# SuperCapacitor_Schmatic.net
KiCad netlist of a schematic drawn in EAGLE
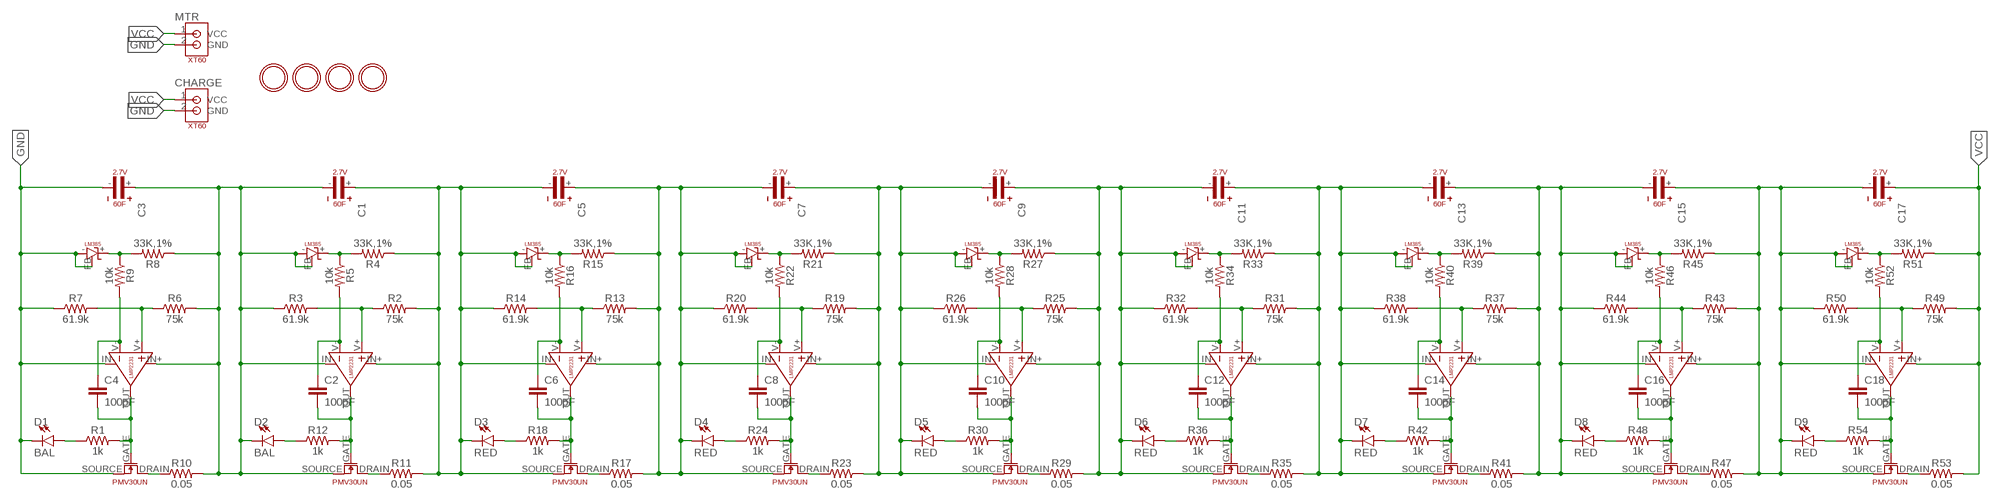
[diagram p0: schematic, sheet 1]

(export (version "E")
  (design (tool "Eeschema 10.0.6"))
  (components
    (comp (ref "C1")
      (value "2.7V 60F")
      (footprint "eagle-import:2.7V_60F")
      (libsource (lib "eagle-import") (part "2.7V_60F"))
    )
    (comp (ref "C2")
      (value "100pF")
      (footprint "eagle-import:0603")
      (libsource (lib "eagle-import") (part "100PF-0603-50V-5%"))
    )
    (comp (ref "C3")
      (value "2.7V 60F")
      (footprint "eagle-import:2.7V_60F")
      (libsource (lib "eagle-import") (part "2.7V_60F"))
    )
    (comp (ref "C4")
      (value "100pF")
      (footprint "eagle-import:0603")
      (libsource (lib "eagle-import") (part "100PF-0603-50V-5%"))
    )
    (comp (ref "C5")
      (value "2.7V 60F")
      (footprint "eagle-import:2.7V_60F")
      (libsource (lib "eagle-import") (part "2.7V_60F"))
    )
    (comp (ref "C6")
      (value "100pF")
      (footprint "eagle-import:0603")
      (libsource (lib "eagle-import") (part "100PF-0603-50V-5%"))
    )
    (comp (ref "C7")
      (value "2.7V 60F")
      (footprint "eagle-import:2.7V_60F")
      (libsource (lib "eagle-import") (part "2.7V_60F"))
    )
    (comp (ref "C8")
      (value "100pF")
      (footprint "eagle-import:0603")
      (libsource (lib "eagle-import") (part "100PF-0603-50V-5%"))
    )
    (comp (ref "C9")
      (value "2.7V 60F")
      (footprint "eagle-import:2.7V_60F")
      (libsource (lib "eagle-import") (part "2.7V_60F"))
    )
    (comp (ref "C10")
      (value "100pF")
      (footprint "eagle-import:0603")
      (libsource (lib "eagle-import") (part "100PF-0603-50V-5%"))
    )
    (comp (ref "C11")
      (value "2.7V 60F")
      (footprint "eagle-import:2.7V_60F")
      (libsource (lib "eagle-import") (part "2.7V_60F"))
    )
    (comp (ref "C12")
      (value "100pF")
      (footprint "eagle-import:0603")
      (libsource (lib "eagle-import") (part "100PF-0603-50V-5%"))
    )
    (comp (ref "C13")
      (value "2.7V 60F")
      (footprint "eagle-import:2.7V_60F")
      (libsource (lib "eagle-import") (part "2.7V_60F"))
    )
    (comp (ref "C14")
      (value "100pF")
      (footprint "eagle-import:0603")
      (libsource (lib "eagle-import") (part "100PF-0603-50V-5%"))
    )
    (comp (ref "C15")
      (value "2.7V 60F")
      (footprint "eagle-import:2.7V_60F")
      (libsource (lib "eagle-import") (part "2.7V_60F"))
    )
    (comp (ref "C16")
      (value "100pF")
      (footprint "eagle-import:0603")
      (libsource (lib "eagle-import") (part "100PF-0603-50V-5%"))
    )
    (comp (ref "C17")
      (value "2.7V 60F")
      (footprint "eagle-import:2.7V_60F")
      (libsource (lib "eagle-import") (part "2.7V_60F"))
    )
    (comp (ref "C18")
      (value "100pF")
      (footprint "eagle-import:0603")
      (libsource (lib "eagle-import") (part "100PF-0603-50V-5%"))
    )
    (comp (ref "CHARGE")
      (value "XT60")
      (footprint "eagle-import:XT60")
      (libsource (lib "eagle-import") (part "XT60"))
    )
    (comp (ref "D1")
      (value "BAL")
      (footprint "eagle-import:LED-0603")
      (libsource (lib "eagle-import") (part "LED-RED0603"))
    )
    (comp (ref "D2")
      (value "BAL")
      (footprint "eagle-import:LED-0603")
      (libsource (lib "eagle-import") (part "LED-RED0603"))
    )
    (comp (ref "D3")
      (value "RED")
      (footprint "eagle-import:LED-0603")
      (libsource (lib "eagle-import") (part "LED-RED0603"))
    )
    (comp (ref "D4")
      (value "RED")
      (footprint "eagle-import:LED-0603")
      (libsource (lib "eagle-import") (part "LED-RED0603"))
    )
    (comp (ref "D5")
      (value "RED")
      (footprint "eagle-import:LED-0603")
      (libsource (lib "eagle-import") (part "LED-RED0603"))
    )
    (comp (ref "D6")
      (value "RED")
      (footprint "eagle-import:LED-0603")
      (libsource (lib "eagle-import") (part "LED-RED0603"))
    )
    (comp (ref "D7")
      (value "RED")
      (footprint "eagle-import:LED-0603")
      (libsource (lib "eagle-import") (part "LED-RED0603"))
    )
    (comp (ref "D8")
      (value "RED")
      (footprint "eagle-import:LED-0603")
      (libsource (lib "eagle-import") (part "LED-RED0603"))
    )
    (comp (ref "D9")
      (value "RED")
      (footprint "eagle-import:LED-0603")
      (libsource (lib "eagle-import") (part "LED-RED0603"))
    )
    (comp (ref "MTR")
      (value "XT60")
      (footprint "eagle-import:XT60")
      (libsource (lib "eagle-import") (part "XT60"))
    )
    (comp (ref "R1")
      (value "1k")
      (footprint "eagle-import:0603")
      (libsource (lib "eagle-import") (part "1KOHM-0603-1/10W-1%"))
    )
    (comp (ref "R2")
      (value "75k")
      (footprint "eagle-import:0603")
      (libsource (lib "eagle-import") (part "75KOHM-0603-1/10W-1%"))
    )
    (comp (ref "R3")
      (value "61.9k")
      (footprint "eagle-import:0603")
      (libsource (lib "eagle-import") (part "75KOHM-0603-1/10W-1%"))
    )
    (comp (ref "R4")
      (value "33K,1%")
      (footprint "eagle-import:0603")
      (libsource (lib "eagle-import") (part "1MOHM-0603-1/4W-5%"))
    )
    (comp (ref "R5")
      (value "10k")
      (footprint "eagle-import:0603")
      (libsource (lib "eagle-import") (part "10KOHM-0603-1/10W-1%"))
    )
    (comp (ref "R6")
      (value "75k")
      (footprint "eagle-import:0603")
      (libsource (lib "eagle-import") (part "75KOHM-0603-1/10W-1%"))
    )
    (comp (ref "R7")
      (value "61.9k")
      (footprint "eagle-import:0603")
      (libsource (lib "eagle-import") (part "75KOHM-0603-1/10W-1%"))
    )
    (comp (ref "R8")
      (value "33K,1%")
      (footprint "eagle-import:0603")
      (libsource (lib "eagle-import") (part "1MOHM-0603-1/4W-5%"))
    )
    (comp (ref "R9")
      (value "10k")
      (footprint "eagle-import:0603")
      (libsource (lib "eagle-import") (part "10KOHM-0603-1/10W-1%"))
    )
    (comp (ref "R10")
      (value "0.05")
      (footprint "eagle-import:2512")
      (libsource (lib "eagle-import") (part "0.05OHM-2512-3W-1%"))
    )
    (comp (ref "R11")
      (value "0.05")
      (footprint "eagle-import:2512")
      (libsource (lib "eagle-import") (part "0.05OHM-2512-3W-1%"))
    )
    (comp (ref "R12")
      (value "1k")
      (footprint "eagle-import:0603")
      (libsource (lib "eagle-import") (part "1KOHM-0603-1/10W-1%"))
    )
    (comp (ref "R13")
      (value "75k")
      (footprint "eagle-import:0603")
      (libsource (lib "eagle-import") (part "75KOHM-0603-1/10W-1%"))
    )
    (comp (ref "R14")
      (value "61.9k")
      (footprint "eagle-import:0603")
      (libsource (lib "eagle-import") (part "75KOHM-0603-1/10W-1%"))
    )
    (comp (ref "R15")
      (value "33K,1%")
      (footprint "eagle-import:0603")
      (libsource (lib "eagle-import") (part "1MOHM-0603-1/4W-5%"))
    )
    (comp (ref "R16")
      (value "10k")
      (footprint "eagle-import:0603")
      (libsource (lib "eagle-import") (part "10KOHM-0603-1/10W-1%"))
    )
    (comp (ref "R17")
      (value "0.05")
      (footprint "eagle-import:2512")
      (libsource (lib "eagle-import") (part "0.05OHM-2512-3W-1%"))
    )
    (comp (ref "R18")
      (value "1k")
      (footprint "eagle-import:0603")
      (libsource (lib "eagle-import") (part "1KOHM-0603-1/10W-1%"))
    )
    (comp (ref "R19")
      (value "75k")
      (footprint "eagle-import:0603")
      (libsource (lib "eagle-import") (part "75KOHM-0603-1/10W-1%"))
    )
    (comp (ref "R20")
      (value "61.9k")
      (footprint "eagle-import:0603")
      (libsource (lib "eagle-import") (part "75KOHM-0603-1/10W-1%"))
    )
    (comp (ref "R21")
      (value "33K,1%")
      (footprint "eagle-import:0603")
      (libsource (lib "eagle-import") (part "1MOHM-0603-1/4W-5%"))
    )
    (comp (ref "R22")
      (value "10k")
      (footprint "eagle-import:0603")
      (libsource (lib "eagle-import") (part "10KOHM-0603-1/10W-1%"))
    )
    (comp (ref "R23")
      (value "0.05")
      (footprint "eagle-import:2512")
      (libsource (lib "eagle-import") (part "0.05OHM-2512-3W-1%"))
    )
    (comp (ref "R24")
      (value "1k")
      (footprint "eagle-import:0603")
      (libsource (lib "eagle-import") (part "1KOHM-0603-1/10W-1%"))
    )
    (comp (ref "R25")
      (value "75k")
      (footprint "eagle-import:0603")
      (libsource (lib "eagle-import") (part "75KOHM-0603-1/10W-1%"))
    )
    (comp (ref "R26")
      (value "61.9k")
      (footprint "eagle-import:0603")
      (libsource (lib "eagle-import") (part "75KOHM-0603-1/10W-1%"))
    )
    (comp (ref "R27")
      (value "33K,1%")
      (footprint "eagle-import:0603")
      (libsource (lib "eagle-import") (part "1MOHM-0603-1/4W-5%"))
    )
    (comp (ref "R28")
      (value "10k")
      (footprint "eagle-import:0603")
      (libsource (lib "eagle-import") (part "10KOHM-0603-1/10W-1%"))
    )
    (comp (ref "R29")
      (value "0.05")
      (footprint "eagle-import:2512")
      (libsource (lib "eagle-import") (part "0.05OHM-2512-3W-1%"))
    )
    (comp (ref "R30")
      (value "1k")
      (footprint "eagle-import:0603")
      (libsource (lib "eagle-import") (part "1KOHM-0603-1/10W-1%"))
    )
    (comp (ref "R31")
      (value "75k")
      (footprint "eagle-import:0603")
      (libsource (lib "eagle-import") (part "75KOHM-0603-1/10W-1%"))
    )
    (comp (ref "R32")
      (value "61.9k")
      (footprint "eagle-import:0603")
      (libsource (lib "eagle-import") (part "75KOHM-0603-1/10W-1%"))
    )
    (comp (ref "R33")
      (value "33K,1%")
      (footprint "eagle-import:0603")
      (libsource (lib "eagle-import") (part "1MOHM-0603-1/4W-5%"))
    )
    (comp (ref "R34")
      (value "10k")
      (footprint "eagle-import:0603")
      (libsource (lib "eagle-import") (part "10KOHM-0603-1/10W-1%"))
    )
    (comp (ref "R35")
      (value "0.05")
      (footprint "eagle-import:2512")
      (libsource (lib "eagle-import") (part "0.05OHM-2512-3W-1%"))
    )
    (comp (ref "R36")
      (value "1k")
      (footprint "eagle-import:0603")
      (libsource (lib "eagle-import") (part "1KOHM-0603-1/10W-1%"))
    )
    (comp (ref "R37")
      (value "75k")
      (footprint "eagle-import:0603")
      (libsource (lib "eagle-import") (part "75KOHM-0603-1/10W-1%"))
    )
    (comp (ref "R38")
      (value "61.9k")
      (footprint "eagle-import:0603")
      (libsource (lib "eagle-import") (part "75KOHM-0603-1/10W-1%"))
    )
    (comp (ref "R39")
      (value "33K,1%")
      (footprint "eagle-import:0603")
      (libsource (lib "eagle-import") (part "1MOHM-0603-1/4W-5%"))
    )
    (comp (ref "R40")
      (value "10k")
      (footprint "eagle-import:0603")
      (libsource (lib "eagle-import") (part "10KOHM-0603-1/10W-1%"))
    )
    (comp (ref "R41")
      (value "0.05")
      (footprint "eagle-import:2512")
      (libsource (lib "eagle-import") (part "0.05OHM-2512-3W-1%"))
    )
    (comp (ref "R42")
      (value "1k")
      (footprint "eagle-import:0603")
      (libsource (lib "eagle-import") (part "1KOHM-0603-1/10W-1%"))
    )
    (comp (ref "R43")
      (value "75k")
      (footprint "eagle-import:0603")
      (libsource (lib "eagle-import") (part "75KOHM-0603-1/10W-1%"))
    )
    (comp (ref "R44")
      (value "61.9k")
      (footprint "eagle-import:0603")
      (libsource (lib "eagle-import") (part "75KOHM-0603-1/10W-1%"))
    )
    (comp (ref "R45")
      (value "33K,1%")
      (footprint "eagle-import:0603")
      (libsource (lib "eagle-import") (part "1MOHM-0603-1/4W-5%"))
    )
    (comp (ref "R46")
      (value "10k")
      (footprint "eagle-import:0603")
      (libsource (lib "eagle-import") (part "10KOHM-0603-1/10W-1%"))
    )
    (comp (ref "R47")
      (value "0.05")
      (footprint "eagle-import:2512")
      (libsource (lib "eagle-import") (part "0.05OHM-2512-3W-1%"))
    )
    (comp (ref "R48")
      (value "1k")
      (footprint "eagle-import:0603")
      (libsource (lib "eagle-import") (part "1KOHM-0603-1/10W-1%"))
    )
    (comp (ref "R49")
      (value "75k")
      (footprint "eagle-import:0603")
      (libsource (lib "eagle-import") (part "75KOHM-0603-1/10W-1%"))
    )
    (comp (ref "R50")
      (value "61.9k")
      (footprint "eagle-import:0603")
      (libsource (lib "eagle-import") (part "75KOHM-0603-1/10W-1%"))
    )
    (comp (ref "R51")
      (value "33K,1%")
      (footprint "eagle-import:0603")
      (libsource (lib "eagle-import") (part "1MOHM-0603-1/4W-5%"))
    )
    (comp (ref "R52")
      (value "10k")
      (footprint "eagle-import:0603")
      (libsource (lib "eagle-import") (part "10KOHM-0603-1/10W-1%"))
    )
    (comp (ref "R53")
      (value "0.05")
      (footprint "eagle-import:2512")
      (libsource (lib "eagle-import") (part "0.05OHM-2512-3W-1%"))
    )
    (comp (ref "R54")
      (value "1k")
      (footprint "eagle-import:0603")
      (libsource (lib "eagle-import") (part "1KOHM-0603-1/10W-1%"))
    )
    (comp (ref "U$1")
      (value "LMP2231")
      (footprint "eagle-import:LMP2231_SOT23_5")
      (libsource (lib "eagle-import") (part "LMP2231"))
    )
    (comp (ref "U$2")
      (value "LM385")
      (footprint "eagle-import:LM385_SOT23")
      (libsource (lib "eagle-import") (part "LM385"))
    )
    (comp (ref "U$3")
      (value "PMV30UN_MOS")
      (footprint "eagle-import:PMV30UN_SOT23")
      (libsource (lib "eagle-import") (part "PMV30UN_MOS"))
    )
    (comp (ref "U$4")
      (value "LMP2231")
      (footprint "eagle-import:LMP2231_SOT23_5")
      (libsource (lib "eagle-import") (part "LMP2231"))
    )
    (comp (ref "U$5")
      (value "LM385")
      (footprint "eagle-import:LM385_SOT23")
      (libsource (lib "eagle-import") (part "LM385"))
    )
    (comp (ref "U$6")
      (value "PMV30UN_MOS")
      (footprint "eagle-import:PMV30UN_SOT23")
      (libsource (lib "eagle-import") (part "PMV30UN_MOS"))
    )
    (comp (ref "U$7")
      (value "LMP2231")
      (footprint "eagle-import:LMP2231_SOT23_5")
      (libsource (lib "eagle-import") (part "LMP2231"))
    )
    (comp (ref "U$8")
      (value "LM385")
      (footprint "eagle-import:LM385_SOT23")
      (libsource (lib "eagle-import") (part "LM385"))
    )
    (comp (ref "U$9")
      (value "PMV30UN_MOS")
      (footprint "eagle-import:PMV30UN_SOT23")
      (libsource (lib "eagle-import") (part "PMV30UN_MOS"))
    )
    (comp (ref "U$10")
      (value "LMP2231")
      (footprint "eagle-import:LMP2231_SOT23_5")
      (libsource (lib "eagle-import") (part "LMP2231"))
    )
    (comp (ref "U$11")
      (value "LM385")
      (footprint "eagle-import:LM385_SOT23")
      (libsource (lib "eagle-import") (part "LM385"))
    )
    (comp (ref "U$12")
      (value "PMV30UN_MOS")
      (footprint "eagle-import:PMV30UN_SOT23")
      (libsource (lib "eagle-import") (part "PMV30UN_MOS"))
    )
    (comp (ref "U$13")
      (value "LMP2231")
      (footprint "eagle-import:LMP2231_SOT23_5")
      (libsource (lib "eagle-import") (part "LMP2231"))
    )
    (comp (ref "U$14")
      (value "LM385")
      (footprint "eagle-import:LM385_SOT23")
      (libsource (lib "eagle-import") (part "LM385"))
    )
    (comp (ref "U$15")
      (value "PMV30UN_MOS")
      (footprint "eagle-import:PMV30UN_SOT23")
      (libsource (lib "eagle-import") (part "PMV30UN_MOS"))
    )
    (comp (ref "U$16")
      (value "LMP2231")
      (footprint "eagle-import:LMP2231_SOT23_5")
      (libsource (lib "eagle-import") (part "LMP2231"))
    )
    (comp (ref "U$17")
      (value "LM385")
      (footprint "eagle-import:LM385_SOT23")
      (libsource (lib "eagle-import") (part "LM385"))
    )
    (comp (ref "U$18")
      (value "PMV30UN_MOS")
      (footprint "eagle-import:PMV30UN_SOT23")
      (libsource (lib "eagle-import") (part "PMV30UN_MOS"))
    )
    (comp (ref "U$19")
      (value "LMP2231")
      (footprint "eagle-import:LMP2231_SOT23_5")
      (libsource (lib "eagle-import") (part "LMP2231"))
    )
    (comp (ref "U$20")
      (value "LM385")
      (footprint "eagle-import:LM385_SOT23")
      (libsource (lib "eagle-import") (part "LM385"))
    )
    (comp (ref "U$21")
      (value "PMV30UN_MOS")
      (footprint "eagle-import:PMV30UN_SOT23")
      (libsource (lib "eagle-import") (part "PMV30UN_MOS"))
    )
    (comp (ref "U$22")
      (value "LMP2231")
      (footprint "eagle-import:LMP2231_SOT23_5")
      (libsource (lib "eagle-import") (part "LMP2231"))
    )
    (comp (ref "U$23")
      (value "LM385")
      (footprint "eagle-import:LM385_SOT23")
      (libsource (lib "eagle-import") (part "LM385"))
    )
    (comp (ref "U$24")
      (value "PMV30UN_MOS")
      (footprint "eagle-import:PMV30UN_SOT23")
      (libsource (lib "eagle-import") (part "PMV30UN_MOS"))
    )
    (comp (ref "U$25")
      (value "LMP2231")
      (footprint "eagle-import:LMP2231_SOT23_5")
      (libsource (lib "eagle-import") (part "LMP2231"))
    )
    (comp (ref "U$26")
      (value "LM385")
      (footprint "eagle-import:LM385_SOT23")
      (libsource (lib "eagle-import") (part "LM385"))
    )
    (comp (ref "U$27")
      (value "PMV30UN_MOS")
      (footprint "eagle-import:PMV30UN_SOT23")
      (libsource (lib "eagle-import") (part "PMV30UN_MOS"))
    )
    (comp (ref "U$30")
      (value "M5")
      (footprint "eagle-import:M5")
      (libsource (lib "eagle-import") (part "M5"))
    )
    (comp (ref "U$31")
      (value "M5")
      (footprint "eagle-import:M5")
      (libsource (lib "eagle-import") (part "M5"))
    )
    (comp (ref "U$32")
      (value "M5")
      (footprint "eagle-import:M5")
      (libsource (lib "eagle-import") (part "M5"))
    )
    (comp (ref "U$33")
      (value "M5")
      (footprint "eagle-import:M5")
      (libsource (lib "eagle-import") (part "M5"))
    )
  )
  (nets
    (net (code "1") (name "GND") (class "Default")
      (node (ref "C3") (pin "-") (pinfunction "-_-") (pintype "bidirectional"))
      (node (ref "CHARGE") (pin "2") (pinfunction "GND_2") (pintype "bidirectional"))
      (node (ref "D1") (pin "C") (pinfunction "C_C") (pintype "passive"))
      (node (ref "MTR") (pin "2") (pinfunction "GND_2") (pintype "bidirectional"))
      (node (ref "R7") (pin "1") (pinfunction "1_1") (pintype "passive"))
      (node (ref "U$4") (pin "IN-") (pinfunction "IN-_IN-") (pintype "bidirectional"))
      (node (ref "U$5") (pin "-") (pinfunction "-_-") (pintype "bidirectional"))
      (node (ref "U$5") (pin "FB") (pinfunction "FB_FB") (pintype "bidirectional"))
      (node (ref "U$6") (pin "SOURCE") (pinfunction "SOURCE_SOURCE") (pintype "bidirectional"))
    )
    (net (code "2") (name "Net-(C2-Pad1)") (class "Default")
      (node (ref "C2") (pin "1") (pinfunction "1_1") (pintype "passive"))
      (node (ref "R5") (pin "2") (pinfunction "2_2") (pintype "passive"))
      (node (ref "U$1") (pin "V-") (pinfunction "V-_V-") (pintype "bidirectional"))
    )
    (net (code "3") (name "Net-(C2-Pad2)") (class "Default")
      (node (ref "C2") (pin "2") (pinfunction "2_2") (pintype "passive"))
      (node (ref "R12") (pin "2") (pinfunction "2_2") (pintype "passive"))
      (node (ref "U$1") (pin "OUT") (pinfunction "OUT_OUT") (pintype "bidirectional"))
      (node (ref "U$3") (pin "GATE") (pinfunction "GATE_GATE") (pintype "bidirectional"))
    )
    (net (code "4") (name "Net-(C4-Pad1)") (class "Default")
      (node (ref "C4") (pin "1") (pinfunction "1_1") (pintype "passive"))
      (node (ref "R9") (pin "2") (pinfunction "2_2") (pintype "passive"))
      (node (ref "U$4") (pin "V-") (pinfunction "V-_V-") (pintype "bidirectional"))
    )
    (net (code "5") (name "Net-(C4-Pad2)") (class "Default")
      (node (ref "C4") (pin "2") (pinfunction "2_2") (pintype "passive"))
      (node (ref "R1") (pin "2") (pinfunction "2_2") (pintype "passive"))
      (node (ref "U$4") (pin "OUT") (pinfunction "OUT_OUT") (pintype "bidirectional"))
      (node (ref "U$6") (pin "GATE") (pinfunction "GATE_GATE") (pintype "bidirectional"))
    )
    (net (code "6") (name "Net-(C6-Pad1)") (class "Default")
      (node (ref "C6") (pin "1") (pinfunction "1_1") (pintype "passive"))
      (node (ref "R16") (pin "2") (pinfunction "2_2") (pintype "passive"))
      (node (ref "U$7") (pin "V-") (pinfunction "V-_V-") (pintype "bidirectional"))
    )
    (net (code "7") (name "Net-(C6-Pad2)") (class "Default")
      (node (ref "C6") (pin "2") (pinfunction "2_2") (pintype "passive"))
      (node (ref "R18") (pin "2") (pinfunction "2_2") (pintype "passive"))
      (node (ref "U$7") (pin "OUT") (pinfunction "OUT_OUT") (pintype "bidirectional"))
      (node (ref "U$9") (pin "GATE") (pinfunction "GATE_GATE") (pintype "bidirectional"))
    )
    (net (code "8") (name "Net-(C8-Pad1)") (class "Default")
      (node (ref "C8") (pin "1") (pinfunction "1_1") (pintype "passive"))
      (node (ref "R22") (pin "2") (pinfunction "2_2") (pintype "passive"))
      (node (ref "U$10") (pin "V-") (pinfunction "V-_V-") (pintype "bidirectional"))
    )
    (net (code "9") (name "Net-(C8-Pad2)") (class "Default")
      (node (ref "C8") (pin "2") (pinfunction "2_2") (pintype "passive"))
      (node (ref "R24") (pin "2") (pinfunction "2_2") (pintype "passive"))
      (node (ref "U$10") (pin "OUT") (pinfunction "OUT_OUT") (pintype "bidirectional"))
      (node (ref "U$12") (pin "GATE") (pinfunction "GATE_GATE") (pintype "bidirectional"))
    )
    (net (code "10") (name "Net-(C10-Pad1)") (class "Default")
      (node (ref "C10") (pin "1") (pinfunction "1_1") (pintype "passive"))
      (node (ref "R28") (pin "2") (pinfunction "2_2") (pintype "passive"))
      (node (ref "U$13") (pin "V-") (pinfunction "V-_V-") (pintype "bidirectional"))
    )
    (net (code "11") (name "Net-(C10-Pad2)") (class "Default")
      (node (ref "C10") (pin "2") (pinfunction "2_2") (pintype "passive"))
      (node (ref "R30") (pin "2") (pinfunction "2_2") (pintype "passive"))
      (node (ref "U$13") (pin "OUT") (pinfunction "OUT_OUT") (pintype "bidirectional"))
      (node (ref "U$15") (pin "GATE") (pinfunction "GATE_GATE") (pintype "bidirectional"))
    )
    (net (code "12") (name "Net-(C12-Pad1)") (class "Default")
      (node (ref "C12") (pin "1") (pinfunction "1_1") (pintype "passive"))
      (node (ref "R34") (pin "2") (pinfunction "2_2") (pintype "passive"))
      (node (ref "U$16") (pin "V-") (pinfunction "V-_V-") (pintype "bidirectional"))
    )
    (net (code "13") (name "Net-(C12-Pad2)") (class "Default")
      (node (ref "C12") (pin "2") (pinfunction "2_2") (pintype "passive"))
      (node (ref "R36") (pin "2") (pinfunction "2_2") (pintype "passive"))
      (node (ref "U$16") (pin "OUT") (pinfunction "OUT_OUT") (pintype "bidirectional"))
      (node (ref "U$18") (pin "GATE") (pinfunction "GATE_GATE") (pintype "bidirectional"))
    )
    (net (code "14") (name "Net-(C14-Pad1)") (class "Default")
      (node (ref "C14") (pin "1") (pinfunction "1_1") (pintype "passive"))
      (node (ref "R40") (pin "2") (pinfunction "2_2") (pintype "passive"))
      (node (ref "U$19") (pin "V-") (pinfunction "V-_V-") (pintype "bidirectional"))
    )
    (net (code "15") (name "Net-(C14-Pad2)") (class "Default")
      (node (ref "C14") (pin "2") (pinfunction "2_2") (pintype "passive"))
      (node (ref "R42") (pin "2") (pinfunction "2_2") (pintype "passive"))
      (node (ref "U$19") (pin "OUT") (pinfunction "OUT_OUT") (pintype "bidirectional"))
      (node (ref "U$21") (pin "GATE") (pinfunction "GATE_GATE") (pintype "bidirectional"))
    )
    (net (code "16") (name "Net-(C16-Pad1)") (class "Default")
      (node (ref "C16") (pin "1") (pinfunction "1_1") (pintype "passive"))
      (node (ref "R46") (pin "2") (pinfunction "2_2") (pintype "passive"))
      (node (ref "U$22") (pin "V-") (pinfunction "V-_V-") (pintype "bidirectional"))
    )
    (net (code "17") (name "Net-(C16-Pad2)") (class "Default")
      (node (ref "C16") (pin "2") (pinfunction "2_2") (pintype "passive"))
      (node (ref "R48") (pin "2") (pinfunction "2_2") (pintype "passive"))
      (node (ref "U$22") (pin "OUT") (pinfunction "OUT_OUT") (pintype "bidirectional"))
      (node (ref "U$24") (pin "GATE") (pinfunction "GATE_GATE") (pintype "bidirectional"))
    )
    (net (code "18") (name "Net-(C18-Pad1)") (class "Default")
      (node (ref "C18") (pin "1") (pinfunction "1_1") (pintype "passive"))
      (node (ref "R52") (pin "2") (pinfunction "2_2") (pintype "passive"))
      (node (ref "U$25") (pin "V-") (pinfunction "V-_V-") (pintype "bidirectional"))
    )
    (net (code "19") (name "Net-(C18-Pad2)") (class "Default")
      (node (ref "C18") (pin "2") (pinfunction "2_2") (pintype "passive"))
      (node (ref "R54") (pin "2") (pinfunction "2_2") (pintype "passive"))
      (node (ref "U$25") (pin "OUT") (pinfunction "OUT_OUT") (pintype "bidirectional"))
      (node (ref "U$27") (pin "GATE") (pinfunction "GATE_GATE") (pintype "bidirectional"))
    )
    (net (code "20") (name "Net-(D1-PadA)") (class "Default")
      (node (ref "D1") (pin "A") (pinfunction "A_A") (pintype "passive"))
      (node (ref "R1") (pin "1") (pinfunction "1_1") (pintype "passive"))
    )
    (net (code "21") (name "Net-(D2-PadA)") (class "Default")
      (node (ref "D2") (pin "A") (pinfunction "A_A") (pintype "passive"))
      (node (ref "R12") (pin "1") (pinfunction "1_1") (pintype "passive"))
    )
    (net (code "22") (name "Net-(D3-PadA)") (class "Default")
      (node (ref "D3") (pin "A") (pinfunction "A_A") (pintype "passive"))
      (node (ref "R18") (pin "1") (pinfunction "1_1") (pintype "passive"))
    )
    (net (code "23") (name "Net-(D4-PadA)") (class "Default")
      (node (ref "D4") (pin "A") (pinfunction "A_A") (pintype "passive"))
      (node (ref "R24") (pin "1") (pinfunction "1_1") (pintype "passive"))
    )
    (net (code "24") (name "Net-(D5-PadA)") (class "Default")
      (node (ref "D5") (pin "A") (pinfunction "A_A") (pintype "passive"))
      (node (ref "R30") (pin "1") (pinfunction "1_1") (pintype "passive"))
    )
    (net (code "25") (name "Net-(D6-PadA)") (class "Default")
      (node (ref "D6") (pin "A") (pinfunction "A_A") (pintype "passive"))
      (node (ref "R36") (pin "1") (pinfunction "1_1") (pintype "passive"))
    )
    (net (code "26") (name "Net-(D7-PadA)") (class "Default")
      (node (ref "D7") (pin "A") (pinfunction "A_A") (pintype "passive"))
      (node (ref "R42") (pin "1") (pinfunction "1_1") (pintype "passive"))
    )
    (net (code "27") (name "Net-(D8-PadA)") (class "Default")
      (node (ref "D8") (pin "A") (pinfunction "A_A") (pintype "passive"))
      (node (ref "R48") (pin "1") (pinfunction "1_1") (pintype "passive"))
    )
    (net (code "28") (name "Net-(D9-PadA)") (class "Default")
      (node (ref "D9") (pin "A") (pinfunction "A_A") (pintype "passive"))
      (node (ref "R54") (pin "1") (pinfunction "1_1") (pintype "passive"))
    )
    (net (code "29") (name "Net-(R2-Pad1)") (class "Default")
      (node (ref "R2") (pin "1") (pinfunction "1_1") (pintype "passive"))
      (node (ref "R3") (pin "2") (pinfunction "2_2") (pintype "passive"))
      (node (ref "U$1") (pin "V+") (pinfunction "V+_V+") (pintype "bidirectional"))
    )
    (net (code "30") (name "Net-(R4-Pad2)") (class "Default")
      (node (ref "R4") (pin "2") (pinfunction "2_2") (pintype "passive"))
      (node (ref "R5") (pin "1") (pinfunction "1_1") (pintype "passive"))
      (node (ref "U$2") (pin "+") (pinfunction "+_+") (pintype "bidirectional"))
    )
    (net (code "31") (name "Net-(R6-Pad1)") (class "Default")
      (node (ref "R6") (pin "1") (pinfunction "1_1") (pintype "passive"))
      (node (ref "R7") (pin "2") (pinfunction "2_2") (pintype "passive"))
      (node (ref "U$4") (pin "V+") (pinfunction "V+_V+") (pintype "bidirectional"))
    )
    (net (code "32") (name "Net-(R8-Pad2)") (class "Default")
      (node (ref "R8") (pin "2") (pinfunction "2_2") (pintype "passive"))
      (node (ref "R9") (pin "1") (pinfunction "1_1") (pintype "passive"))
      (node (ref "U$5") (pin "+") (pinfunction "+_+") (pintype "bidirectional"))
    )
    (net (code "33") (name "Net-(R10-1)") (class "Default")
      (node (ref "R10") (pin "P$1") (pinfunction "1_P$1") (pintype "passive"))
      (node (ref "U$6") (pin "DRAIN") (pinfunction "DRAIN_DRAIN") (pintype "bidirectional"))
    )
    (net (code "34") (name "Net-(R10-2)") (class "Default")
      (node (ref "C1") (pin "-") (pinfunction "-_-") (pintype "bidirectional"))
      (node (ref "C3") (pin "+") (pinfunction "+_+") (pintype "bidirectional"))
      (node (ref "D2") (pin "C") (pinfunction "C_C") (pintype "passive"))
      (node (ref "R10") (pin "P$2") (pinfunction "2_P$2") (pintype "passive"))
      (node (ref "R3") (pin "1") (pinfunction "1_1") (pintype "passive"))
      (node (ref "R6") (pin "2") (pinfunction "2_2") (pintype "passive"))
      (node (ref "R8") (pin "1") (pinfunction "1_1") (pintype "passive"))
      (node (ref "U$1") (pin "IN-") (pinfunction "IN-_IN-") (pintype "bidirectional"))
      (node (ref "U$2") (pin "-") (pinfunction "-_-") (pintype "bidirectional"))
      (node (ref "U$2") (pin "FB") (pinfunction "FB_FB") (pintype "bidirectional"))
      (node (ref "U$3") (pin "SOURCE") (pinfunction "SOURCE_SOURCE") (pintype "bidirectional"))
      (node (ref "U$4") (pin "IN+") (pinfunction "IN+_IN+") (pintype "bidirectional"))
    )
    (net (code "35") (name "Net-(R11-1)") (class "Default")
      (node (ref "R11") (pin "P$1") (pinfunction "1_P$1") (pintype "passive"))
      (node (ref "U$3") (pin "DRAIN") (pinfunction "DRAIN_DRAIN") (pintype "bidirectional"))
    )
    (net (code "36") (name "Net-(R11-2)") (class "Default")
      (node (ref "C1") (pin "+") (pinfunction "+_+") (pintype "bidirectional"))
      (node (ref "C5") (pin "-") (pinfunction "-_-") (pintype "bidirectional"))
      (node (ref "D3") (pin "C") (pinfunction "C_C") (pintype "passive"))
      (node (ref "R11") (pin "P$2") (pinfunction "2_P$2") (pintype "passive"))
      (node (ref "R14") (pin "1") (pinfunction "1_1") (pintype "passive"))
      (node (ref "R2") (pin "2") (pinfunction "2_2") (pintype "passive"))
      (node (ref "R4") (pin "1") (pinfunction "1_1") (pintype "passive"))
      (node (ref "U$1") (pin "IN+") (pinfunction "IN+_IN+") (pintype "bidirectional"))
      (node (ref "U$7") (pin "IN-") (pinfunction "IN-_IN-") (pintype "bidirectional"))
      (node (ref "U$8") (pin "-") (pinfunction "-_-") (pintype "bidirectional"))
      (node (ref "U$8") (pin "FB") (pinfunction "FB_FB") (pintype "bidirectional"))
      (node (ref "U$9") (pin "SOURCE") (pinfunction "SOURCE_SOURCE") (pintype "bidirectional"))
    )
    (net (code "37") (name "Net-(R13-Pad1)") (class "Default")
      (node (ref "R13") (pin "1") (pinfunction "1_1") (pintype "passive"))
      (node (ref "R14") (pin "2") (pinfunction "2_2") (pintype "passive"))
      (node (ref "U$7") (pin "V+") (pinfunction "V+_V+") (pintype "bidirectional"))
    )
    (net (code "38") (name "Net-(R15-Pad2)") (class "Default")
      (node (ref "R15") (pin "2") (pinfunction "2_2") (pintype "passive"))
      (node (ref "R16") (pin "1") (pinfunction "1_1") (pintype "passive"))
      (node (ref "U$8") (pin "+") (pinfunction "+_+") (pintype "bidirectional"))
    )
    (net (code "39") (name "Net-(R17-1)") (class "Default")
      (node (ref "R17") (pin "P$1") (pinfunction "1_P$1") (pintype "passive"))
      (node (ref "U$9") (pin "DRAIN") (pinfunction "DRAIN_DRAIN") (pintype "bidirectional"))
    )
    (net (code "40") (name "Net-(R17-2)") (class "Default")
      (node (ref "C5") (pin "+") (pinfunction "+_+") (pintype "bidirectional"))
      (node (ref "C7") (pin "-") (pinfunction "-_-") (pintype "bidirectional"))
      (node (ref "D4") (pin "C") (pinfunction "C_C") (pintype "passive"))
      (node (ref "R13") (pin "2") (pinfunction "2_2") (pintype "passive"))
      (node (ref "R15") (pin "1") (pinfunction "1_1") (pintype "passive"))
      (node (ref "R17") (pin "P$2") (pinfunction "2_P$2") (pintype "passive"))
      (node (ref "R20") (pin "1") (pinfunction "1_1") (pintype "passive"))
      (node (ref "U$10") (pin "IN-") (pinfunction "IN-_IN-") (pintype "bidirectional"))
      (node (ref "U$11") (pin "-") (pinfunction "-_-") (pintype "bidirectional"))
      (node (ref "U$11") (pin "FB") (pinfunction "FB_FB") (pintype "bidirectional"))
      (node (ref "U$12") (pin "SOURCE") (pinfunction "SOURCE_SOURCE") (pintype "bidirectional"))
      (node (ref "U$7") (pin "IN+") (pinfunction "IN+_IN+") (pintype "bidirectional"))
    )
    (net (code "41") (name "Net-(R19-Pad1)") (class "Default")
      (node (ref "R19") (pin "1") (pinfunction "1_1") (pintype "passive"))
      (node (ref "R20") (pin "2") (pinfunction "2_2") (pintype "passive"))
      (node (ref "U$10") (pin "V+") (pinfunction "V+_V+") (pintype "bidirectional"))
    )
    (net (code "42") (name "Net-(R21-Pad2)") (class "Default")
      (node (ref "R21") (pin "2") (pinfunction "2_2") (pintype "passive"))
      (node (ref "R22") (pin "1") (pinfunction "1_1") (pintype "passive"))
      (node (ref "U$11") (pin "+") (pinfunction "+_+") (pintype "bidirectional"))
    )
    (net (code "43") (name "Net-(R23-1)") (class "Default")
      (node (ref "R23") (pin "P$1") (pinfunction "1_P$1") (pintype "passive"))
      (node (ref "U$12") (pin "DRAIN") (pinfunction "DRAIN_DRAIN") (pintype "bidirectional"))
    )
    (net (code "44") (name "Net-(R23-2)") (class "Default")
      (node (ref "C7") (pin "+") (pinfunction "+_+") (pintype "bidirectional"))
      (node (ref "C9") (pin "-") (pinfunction "-_-") (pintype "bidirectional"))
      (node (ref "D5") (pin "C") (pinfunction "C_C") (pintype "passive"))
      (node (ref "R19") (pin "2") (pinfunction "2_2") (pintype "passive"))
      (node (ref "R21") (pin "1") (pinfunction "1_1") (pintype "passive"))
      (node (ref "R23") (pin "P$2") (pinfunction "2_P$2") (pintype "passive"))
      (node (ref "R26") (pin "1") (pinfunction "1_1") (pintype "passive"))
      (node (ref "U$10") (pin "IN+") (pinfunction "IN+_IN+") (pintype "bidirectional"))
      (node (ref "U$13") (pin "IN-") (pinfunction "IN-_IN-") (pintype "bidirectional"))
      (node (ref "U$14") (pin "-") (pinfunction "-_-") (pintype "bidirectional"))
      (node (ref "U$14") (pin "FB") (pinfunction "FB_FB") (pintype "bidirectional"))
      (node (ref "U$15") (pin "SOURCE") (pinfunction "SOURCE_SOURCE") (pintype "bidirectional"))
    )
    (net (code "45") (name "Net-(R25-Pad1)") (class "Default")
      (node (ref "R25") (pin "1") (pinfunction "1_1") (pintype "passive"))
      (node (ref "R26") (pin "2") (pinfunction "2_2") (pintype "passive"))
      (node (ref "U$13") (pin "V+") (pinfunction "V+_V+") (pintype "bidirectional"))
    )
    (net (code "46") (name "Net-(R27-Pad2)") (class "Default")
      (node (ref "R27") (pin "2") (pinfunction "2_2") (pintype "passive"))
      (node (ref "R28") (pin "1") (pinfunction "1_1") (pintype "passive"))
      (node (ref "U$14") (pin "+") (pinfunction "+_+") (pintype "bidirectional"))
    )
    (net (code "47") (name "Net-(R29-1)") (class "Default")
      (node (ref "R29") (pin "P$1") (pinfunction "1_P$1") (pintype "passive"))
      (node (ref "U$15") (pin "DRAIN") (pinfunction "DRAIN_DRAIN") (pintype "bidirectional"))
    )
    (net (code "48") (name "Net-(R29-2)") (class "Default")
      (node (ref "C11") (pin "-") (pinfunction "-_-") (pintype "bidirectional"))
      (node (ref "C9") (pin "+") (pinfunction "+_+") (pintype "bidirectional"))
      (node (ref "D6") (pin "C") (pinfunction "C_C") (pintype "passive"))
      (node (ref "R25") (pin "2") (pinfunction "2_2") (pintype "passive"))
      (node (ref "R27") (pin "1") (pinfunction "1_1") (pintype "passive"))
      (node (ref "R29") (pin "P$2") (pinfunction "2_P$2") (pintype "passive"))
      (node (ref "R32") (pin "1") (pinfunction "1_1") (pintype "passive"))
      (node (ref "U$13") (pin "IN+") (pinfunction "IN+_IN+") (pintype "bidirectional"))
      (node (ref "U$16") (pin "IN-") (pinfunction "IN-_IN-") (pintype "bidirectional"))
      (node (ref "U$17") (pin "-") (pinfunction "-_-") (pintype "bidirectional"))
      (node (ref "U$17") (pin "FB") (pinfunction "FB_FB") (pintype "bidirectional"))
      (node (ref "U$18") (pin "SOURCE") (pinfunction "SOURCE_SOURCE") (pintype "bidirectional"))
    )
    (net (code "49") (name "Net-(R31-Pad1)") (class "Default")
      (node (ref "R31") (pin "1") (pinfunction "1_1") (pintype "passive"))
      (node (ref "R32") (pin "2") (pinfunction "2_2") (pintype "passive"))
      (node (ref "U$16") (pin "V+") (pinfunction "V+_V+") (pintype "bidirectional"))
    )
    (net (code "50") (name "Net-(R33-Pad2)") (class "Default")
      (node (ref "R33") (pin "2") (pinfunction "2_2") (pintype "passive"))
      (node (ref "R34") (pin "1") (pinfunction "1_1") (pintype "passive"))
      (node (ref "U$17") (pin "+") (pinfunction "+_+") (pintype "bidirectional"))
    )
    (net (code "51") (name "Net-(R35-1)") (class "Default")
      (node (ref "R35") (pin "P$1") (pinfunction "1_P$1") (pintype "passive"))
      (node (ref "U$18") (pin "DRAIN") (pinfunction "DRAIN_DRAIN") (pintype "bidirectional"))
    )
    (net (code "52") (name "Net-(R35-2)") (class "Default")
      (node (ref "C11") (pin "+") (pinfunction "+_+") (pintype "bidirectional"))
      (node (ref "C13") (pin "-") (pinfunction "-_-") (pintype "bidirectional"))
      (node (ref "D7") (pin "C") (pinfunction "C_C") (pintype "passive"))
      (node (ref "R31") (pin "2") (pinfunction "2_2") (pintype "passive"))
      (node (ref "R33") (pin "1") (pinfunction "1_1") (pintype "passive"))
      (node (ref "R35") (pin "P$2") (pinfunction "2_P$2") (pintype "passive"))
      (node (ref "R38") (pin "1") (pinfunction "1_1") (pintype "passive"))
      (node (ref "U$16") (pin "IN+") (pinfunction "IN+_IN+") (pintype "bidirectional"))
      (node (ref "U$19") (pin "IN-") (pinfunction "IN-_IN-") (pintype "bidirectional"))
      (node (ref "U$20") (pin "-") (pinfunction "-_-") (pintype "bidirectional"))
      (node (ref "U$20") (pin "FB") (pinfunction "FB_FB") (pintype "bidirectional"))
      (node (ref "U$21") (pin "SOURCE") (pinfunction "SOURCE_SOURCE") (pintype "bidirectional"))
    )
    (net (code "53") (name "Net-(R37-Pad1)") (class "Default")
      (node (ref "R37") (pin "1") (pinfunction "1_1") (pintype "passive"))
      (node (ref "R38") (pin "2") (pinfunction "2_2") (pintype "passive"))
      (node (ref "U$19") (pin "V+") (pinfunction "V+_V+") (pintype "bidirectional"))
    )
    (net (code "54") (name "Net-(R39-Pad2)") (class "Default")
      (node (ref "R39") (pin "2") (pinfunction "2_2") (pintype "passive"))
      (node (ref "R40") (pin "1") (pinfunction "1_1") (pintype "passive"))
      (node (ref "U$20") (pin "+") (pinfunction "+_+") (pintype "bidirectional"))
    )
    (net (code "55") (name "Net-(R41-1)") (class "Default")
      (node (ref "R41") (pin "P$1") (pinfunction "1_P$1") (pintype "passive"))
      (node (ref "U$21") (pin "DRAIN") (pinfunction "DRAIN_DRAIN") (pintype "bidirectional"))
    )
    (net (code "56") (name "Net-(R41-2)") (class "Default")
      (node (ref "C13") (pin "+") (pinfunction "+_+") (pintype "bidirectional"))
      (node (ref "C15") (pin "-") (pinfunction "-_-") (pintype "bidirectional"))
      (node (ref "D8") (pin "C") (pinfunction "C_C") (pintype "passive"))
      (node (ref "R37") (pin "2") (pinfunction "2_2") (pintype "passive"))
      (node (ref "R39") (pin "1") (pinfunction "1_1") (pintype "passive"))
      (node (ref "R41") (pin "P$2") (pinfunction "2_P$2") (pintype "passive"))
      (node (ref "R44") (pin "1") (pinfunction "1_1") (pintype "passive"))
      (node (ref "U$19") (pin "IN+") (pinfunction "IN+_IN+") (pintype "bidirectional"))
      (node (ref "U$22") (pin "IN-") (pinfunction "IN-_IN-") (pintype "bidirectional"))
      (node (ref "U$23") (pin "-") (pinfunction "-_-") (pintype "bidirectional"))
      (node (ref "U$23") (pin "FB") (pinfunction "FB_FB") (pintype "bidirectional"))
      (node (ref "U$24") (pin "SOURCE") (pinfunction "SOURCE_SOURCE") (pintype "bidirectional"))
    )
    (net (code "57") (name "Net-(R43-Pad1)") (class "Default")
      (node (ref "R43") (pin "1") (pinfunction "1_1") (pintype "passive"))
      (node (ref "R44") (pin "2") (pinfunction "2_2") (pintype "passive"))
      (node (ref "U$22") (pin "V+") (pinfunction "V+_V+") (pintype "bidirectional"))
    )
    (net (code "58") (name "Net-(R45-Pad2)") (class "Default")
      (node (ref "R45") (pin "2") (pinfunction "2_2") (pintype "passive"))
      (node (ref "R46") (pin "1") (pinfunction "1_1") (pintype "passive"))
      (node (ref "U$23") (pin "+") (pinfunction "+_+") (pintype "bidirectional"))
    )
    (net (code "59") (name "Net-(R47-1)") (class "Default")
      (node (ref "R47") (pin "P$1") (pinfunction "1_P$1") (pintype "passive"))
      (node (ref "U$24") (pin "DRAIN") (pinfunction "DRAIN_DRAIN") (pintype "bidirectional"))
    )
    (net (code "60") (name "Net-(R47-2)") (class "Default")
      (node (ref "C15") (pin "+") (pinfunction "+_+") (pintype "bidirectional"))
      (node (ref "C17") (pin "-") (pinfunction "-_-") (pintype "bidirectional"))
      (node (ref "D9") (pin "C") (pinfunction "C_C") (pintype "passive"))
      (node (ref "R43") (pin "2") (pinfunction "2_2") (pintype "passive"))
      (node (ref "R45") (pin "1") (pinfunction "1_1") (pintype "passive"))
      (node (ref "R47") (pin "P$2") (pinfunction "2_P$2") (pintype "passive"))
      (node (ref "R50") (pin "1") (pinfunction "1_1") (pintype "passive"))
      (node (ref "U$22") (pin "IN+") (pinfunction "IN+_IN+") (pintype "bidirectional"))
      (node (ref "U$25") (pin "IN-") (pinfunction "IN-_IN-") (pintype "bidirectional"))
      (node (ref "U$26") (pin "-") (pinfunction "-_-") (pintype "bidirectional"))
      (node (ref "U$26") (pin "FB") (pinfunction "FB_FB") (pintype "bidirectional"))
      (node (ref "U$27") (pin "SOURCE") (pinfunction "SOURCE_SOURCE") (pintype "bidirectional"))
    )
    (net (code "61") (name "Net-(R49-Pad1)") (class "Default")
      (node (ref "R49") (pin "1") (pinfunction "1_1") (pintype "passive"))
      (node (ref "R50") (pin "2") (pinfunction "2_2") (pintype "passive"))
      (node (ref "U$25") (pin "V+") (pinfunction "V+_V+") (pintype "bidirectional"))
    )
    (net (code "62") (name "Net-(R51-Pad2)") (class "Default")
      (node (ref "R51") (pin "2") (pinfunction "2_2") (pintype "passive"))
      (node (ref "R52") (pin "1") (pinfunction "1_1") (pintype "passive"))
      (node (ref "U$26") (pin "+") (pinfunction "+_+") (pintype "bidirectional"))
    )
    (net (code "63") (name "Net-(R53-1)") (class "Default")
      (node (ref "R53") (pin "P$1") (pinfunction "1_P$1") (pintype "passive"))
      (node (ref "U$27") (pin "DRAIN") (pinfunction "DRAIN_DRAIN") (pintype "bidirectional"))
    )
    (net (code "64") (name "VCC") (class "Default")
      (node (ref "C17") (pin "+") (pinfunction "+_+") (pintype "bidirectional"))
      (node (ref "CHARGE") (pin "1") (pinfunction "VCC_1") (pintype "bidirectional"))
      (node (ref "MTR") (pin "1") (pinfunction "VCC_1") (pintype "bidirectional"))
      (node (ref "R49") (pin "2") (pinfunction "2_2") (pintype "passive"))
      (node (ref "R51") (pin "1") (pinfunction "1_1") (pintype "passive"))
      (node (ref "R53") (pin "P$2") (pinfunction "2_P$2") (pintype "passive"))
      (node (ref "U$25") (pin "IN+") (pinfunction "IN+_IN+") (pintype "bidirectional"))
    )
  )
)
